# Sheet1.net
KiCad netlist of a schematic drawn in Altium Designer
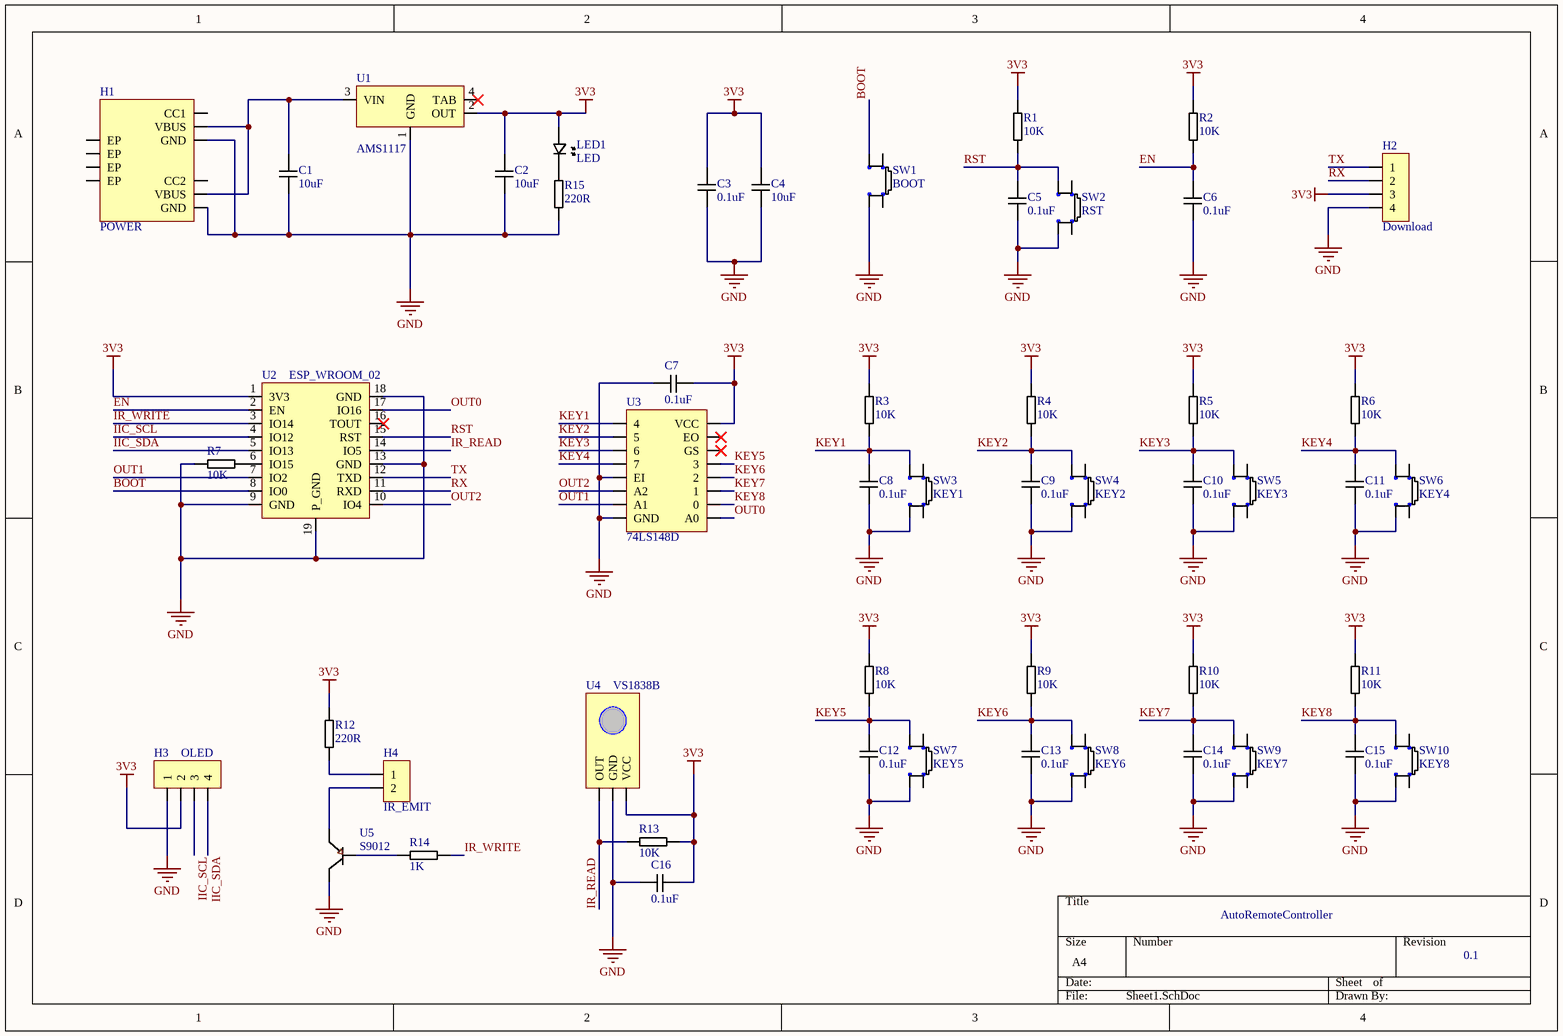
[diagram p0: Sheet1.SchDoc]

(export (version "E")
  (design (tool "Eeschema 10.0.6"))
  (components
    (comp (ref "C1")
      (value "10uF")
      (footprint "Capacity_0805_SMD")
      (libsource (lib "BasicLib") (part "Cap0805"))
    )
    (comp (ref "C2")
      (value "10uF")
      (footprint "Capacity_0805_SMD")
      (libsource (lib "BasicLib") (part "Cap0805"))
    )
    (comp (ref "C3")
      (value "0.1uF")
      (footprint "Capacity_0805_SMD")
      (libsource (lib "BasicLib") (part "Cap0805"))
    )
    (comp (ref "C4")
      (value "10uF")
      (footprint "Capacity_0805_SMD")
      (libsource (lib "BasicLib") (part "Cap0805"))
    )
    (comp (ref "C5")
      (value "0.1uF")
      (footprint "Capacity_0805_SMD")
      (libsource (lib "BasicLib") (part "Cap0805"))
    )
    (comp (ref "C6")
      (value "0.1uF")
      (footprint "Capacity_0805_SMD")
      (libsource (lib "BasicLib") (part "Cap0805"))
    )
    (comp (ref "C7")
      (value "0.1uF")
      (footprint "Capacity_0805_SMD")
      (libsource (lib "BasicLib") (part "Cap0805"))
    )
    (comp (ref "C8")
      (value "0.1uF")
      (footprint "Capacity_0805_SMD")
      (libsource (lib "BasicLib") (part "Cap0805"))
    )
    (comp (ref "C9")
      (value "0.1uF")
      (footprint "Capacity_0805_SMD")
      (libsource (lib "BasicLib") (part "Cap0805"))
    )
    (comp (ref "C10")
      (value "0.1uF")
      (footprint "Capacity_0805_SMD")
      (libsource (lib "BasicLib") (part "Cap0805"))
    )
    (comp (ref "C11")
      (value "0.1uF")
      (footprint "Capacity_0805_SMD")
      (libsource (lib "BasicLib") (part "Cap0805"))
    )
    (comp (ref "C12")
      (value "0.1uF")
      (footprint "Capacity_0805_SMD")
      (libsource (lib "BasicLib") (part "Cap0805"))
    )
    (comp (ref "C13")
      (value "0.1uF")
      (footprint "Capacity_0805_SMD")
      (libsource (lib "BasicLib") (part "Cap0805"))
    )
    (comp (ref "C14")
      (value "0.1uF")
      (footprint "Capacity_0805_SMD")
      (libsource (lib "BasicLib") (part "Cap0805"))
    )
    (comp (ref "C15")
      (value "0.1uF")
      (footprint "Capacity_0805_SMD")
      (libsource (lib "BasicLib") (part "Cap0805"))
    )
    (comp (ref "C16")
      (value "0.1uF")
      (footprint "Capacity_0805_SMD")
      (libsource (lib "BasicLib") (part "Cap0805"))
    )
    (comp (ref "H1")
      (value "POWER")
      (footprint "TYPEC_SMD_6P")
      (libsource (lib "ConnectorLib") (part "TYPEC_6P_SMD"))
    )
    (comp (ref "H2")
      (value "Download")
      (footprint "Header_2.54_1X4_TH")
      (libsource (lib "") (part "Header_2.54mm_1X4_TH_1"))
    )
    (comp (ref "H3")
      (value "OLED")
      (footprint "Header_2.54_1X4_TH")
      (libsource (lib "ConnectorLib") (part "Header_2.54mm_1X4_TH"))
    )
    (comp (ref "H4")
      (value "IR_EMIT")
      (footprint "Header_2.54_1X2_TH")
      (libsource (lib "ConnectorLib") (part "Header_2.54mm_1X2_TH"))
    )
    (comp (ref "LED1") (value "LED") (footprint "LED_0805_SMD") (libsource (lib "BasicLib") (part "LED0805")))
    (comp (ref "R1")
      (value "10K")
      (footprint "Resistance_0805_SMD")
      (libsource (lib "BasicLib") (part "Res0805"))
    )
    (comp (ref "R2")
      (value "10K")
      (footprint "Resistance_0805_SMD")
      (libsource (lib "BasicLib") (part "Res0805"))
    )
    (comp (ref "R3")
      (value "10K")
      (footprint "Resistance_0805_SMD")
      (libsource (lib "BasicLib") (part "Res0805"))
    )
    (comp (ref "R4")
      (value "10K")
      (footprint "Resistance_0805_SMD")
      (libsource (lib "BasicLib") (part "Res0805"))
    )
    (comp (ref "R5")
      (value "10K")
      (footprint "Resistance_0805_SMD")
      (libsource (lib "BasicLib") (part "Res0805"))
    )
    (comp (ref "R6")
      (value "10K")
      (footprint "Resistance_0805_SMD")
      (libsource (lib "BasicLib") (part "Res0805"))
    )
    (comp (ref "R7")
      (value "10K")
      (footprint "Resistance_0805_SMD")
      (libsource (lib "BasicLib") (part "Res0805"))
    )
    (comp (ref "R8")
      (value "10K")
      (footprint "Resistance_0805_SMD")
      (libsource (lib "BasicLib") (part "Res0805"))
    )
    (comp (ref "R9")
      (value "10K")
      (footprint "Resistance_0805_SMD")
      (libsource (lib "BasicLib") (part "Res0805"))
    )
    (comp (ref "R10")
      (value "10K")
      (footprint "Resistance_0805_SMD")
      (libsource (lib "BasicLib") (part "Res0805"))
    )
    (comp (ref "R11")
      (value "10K")
      (footprint "Resistance_0805_SMD")
      (libsource (lib "BasicLib") (part "Res0805"))
    )
    (comp (ref "R12")
      (value "220R")
      (footprint "Resistance_0805_SMD")
      (libsource (lib "BasicLib") (part "Res0805"))
    )
    (comp (ref "R13")
      (value "10K")
      (footprint "Resistance_0805_SMD")
      (libsource (lib "BasicLib") (part "Res0805"))
    )
    (comp (ref "R14")
      (value "1K")
      (footprint "Resistance_0805_SMD")
      (libsource (lib "BasicLib") (part "Res0805"))
    )
    (comp (ref "R15")
      (value "220R")
      (footprint "Resistance_0805_SMD")
      (libsource (lib "BasicLib") (part "Res0805"))
    )
    (comp (ref "SW1")
      (value "BOOT")
      (footprint "SW_6.0*6.0_SMD")
      (libsource (lib "BasicLib") (part "Key_6.0X6.0"))
    )
    (comp (ref "SW2")
      (value "RST")
      (footprint "SW_6.0*6.0_SMD")
      (libsource (lib "BasicLib") (part "Key_6.0X6.0"))
    )
    (comp (ref "SW3")
      (value "KEY1")
      (footprint "SW_6.0*6.0_SMD")
      (libsource (lib "BasicLib") (part "Key_6.0X6.0"))
    )
    (comp (ref "SW4")
      (value "KEY2")
      (footprint "SW_6.0*6.0_SMD")
      (libsource (lib "BasicLib") (part "Key_6.0X6.0"))
    )
    (comp (ref "SW5")
      (value "KEY3")
      (footprint "SW_6.0*6.0_SMD")
      (libsource (lib "BasicLib") (part "Key_6.0X6.0"))
    )
    (comp (ref "SW6")
      (value "KEY4")
      (footprint "SW_6.0*6.0_SMD")
      (libsource (lib "BasicLib") (part "Key_6.0X6.0"))
    )
    (comp (ref "SW7")
      (value "KEY5")
      (footprint "SW_6.0*6.0_SMD")
      (libsource (lib "BasicLib") (part "Key_6.0X6.0"))
    )
    (comp (ref "SW8")
      (value "KEY6")
      (footprint "SW_6.0*6.0_SMD")
      (libsource (lib "BasicLib") (part "Key_6.0X6.0"))
    )
    (comp (ref "SW9")
      (value "KEY7")
      (footprint "SW_6.0*6.0_SMD")
      (libsource (lib "BasicLib") (part "Key_6.0X6.0"))
    )
    (comp (ref "SW10")
      (value "KEY8")
      (footprint "SW_6.0*6.0_SMD")
      (libsource (lib "BasicLib") (part "Key_6.0X6.0"))
    )
    (comp (ref "U1") (value "AMS1117") (footprint "AMS1117") (libsource (lib "ICLib") (part "AMS1117")))
    (comp (ref "U2")
      (value "ESP_WROOM_02")
      (footprint "ESP_WROOM_02")
      (libsource (lib "ESPLib") (part "ESP_WROOM_02"))
    )
    (comp (ref "U3") (value "74LS148D") (footprint "SOIC-16") (libsource (lib "ICLib") (part "74LS148D")))
    (comp (ref "U4") (value "VS1838B") (footprint "VS1838B") (libsource (lib "BasicLib") (part "VS1838B")))
    (comp (ref "U5") (value "S9012") (footprint "SOT-23") (libsource (lib "BasicLib") (part "S9012_PNP")))
  )
  (nets
    (net (code "1") (name "/BOOT") (class "Default")
      (node (ref "SW1") (pin "2") (pinfunction "2_2") (pintype "passive"))
      (node (ref "U2") (pin "8") (pinfunction "IO0_8") (pintype "passive"))
    )
    (net (code "2") (name "/EN") (class "Default")
      (node (ref "C6") (pin "2") (pinfunction "2_2") (pintype "passive"))
      (node (ref "R2") (pin "1") (pinfunction "1_1") (pintype "passive"))
      (node (ref "U2") (pin "2") (pinfunction "EN_2") (pintype "passive"))
    )
    (net (code "3") (name "/IIC_SCL") (class "Default")
      (node (ref "H3") (pin "3") (pinfunction "3_3") (pintype "passive"))
      (node (ref "U2") (pin "4") (pinfunction "IO12_4") (pintype "passive"))
    )
    (net (code "4") (name "/IIC_SDA") (class "Default")
      (node (ref "H3") (pin "4") (pinfunction "4_4") (pintype "passive"))
      (node (ref "U2") (pin "5") (pinfunction "IO13_5") (pintype "passive"))
    )
    (net (code "5") (name "/IR_READ") (class "Default")
      (node (ref "R13") (pin "2") (pinfunction "2_2") (pintype "passive"))
      (node (ref "U2") (pin "14") (pinfunction "IO5_14") (pintype "passive"))
      (node (ref "U4") (pin "1") (pinfunction "OUT_1") (pintype "passive"))
    )
    (net (code "6") (name "/IR_WRITE") (class "Default")
      (node (ref "R14") (pin "2") (pinfunction "2_2") (pintype "passive"))
      (node (ref "U2") (pin "3") (pinfunction "IO14_3") (pintype "passive"))
    )
    (net (code "7") (name "/KEY1") (class "Default")
      (node (ref "C8") (pin "2") (pinfunction "2_2") (pintype "passive"))
      (node (ref "R3") (pin "1") (pinfunction "1_1") (pintype "passive"))
      (node (ref "SW3") (pin "2") (pinfunction "2_2") (pintype "passive"))
      (node (ref "U3") (pin "1") (pinfunction "4_1") (pintype "passive"))
    )
    (net (code "8") (name "/KEY2") (class "Default")
      (node (ref "C9") (pin "2") (pinfunction "2_2") (pintype "passive"))
      (node (ref "R4") (pin "1") (pinfunction "1_1") (pintype "passive"))
      (node (ref "SW4") (pin "2") (pinfunction "2_2") (pintype "passive"))
      (node (ref "U3") (pin "2") (pinfunction "5_2") (pintype "passive"))
    )
    (net (code "9") (name "/KEY3") (class "Default")
      (node (ref "C10") (pin "2") (pinfunction "2_2") (pintype "passive"))
      (node (ref "R5") (pin "1") (pinfunction "1_1") (pintype "passive"))
      (node (ref "SW5") (pin "2") (pinfunction "2_2") (pintype "passive"))
      (node (ref "U3") (pin "3") (pinfunction "6_3") (pintype "passive"))
    )
    (net (code "10") (name "/KEY4") (class "Default")
      (node (ref "C11") (pin "2") (pinfunction "2_2") (pintype "passive"))
      (node (ref "R6") (pin "1") (pinfunction "1_1") (pintype "passive"))
      (node (ref "SW6") (pin "2") (pinfunction "2_2") (pintype "passive"))
      (node (ref "U3") (pin "4") (pinfunction "7_4") (pintype "passive"))
    )
    (net (code "11") (name "/KEY5") (class "Default")
      (node (ref "C12") (pin "2") (pinfunction "2_2") (pintype "passive"))
      (node (ref "R8") (pin "1") (pinfunction "1_1") (pintype "passive"))
      (node (ref "SW7") (pin "2") (pinfunction "2_2") (pintype "passive"))
      (node (ref "U3") (pin "13") (pinfunction "3_13") (pintype "passive"))
    )
    (net (code "12") (name "/KEY6") (class "Default")
      (node (ref "C13") (pin "2") (pinfunction "2_2") (pintype "passive"))
      (node (ref "R9") (pin "1") (pinfunction "1_1") (pintype "passive"))
      (node (ref "SW8") (pin "2") (pinfunction "2_2") (pintype "passive"))
      (node (ref "U3") (pin "12") (pinfunction "2_12") (pintype "passive"))
    )
    (net (code "13") (name "/KEY7") (class "Default")
      (node (ref "C14") (pin "2") (pinfunction "2_2") (pintype "passive"))
      (node (ref "R10") (pin "1") (pinfunction "1_1") (pintype "passive"))
      (node (ref "SW9") (pin "2") (pinfunction "2_2") (pintype "passive"))
      (node (ref "U3") (pin "11") (pinfunction "1_11") (pintype "passive"))
    )
    (net (code "14") (name "/KEY8") (class "Default")
      (node (ref "C15") (pin "2") (pinfunction "2_2") (pintype "passive"))
      (node (ref "R11") (pin "1") (pinfunction "1_1") (pintype "passive"))
      (node (ref "SW10") (pin "2") (pinfunction "2_2") (pintype "passive"))
      (node (ref "U3") (pin "10") (pinfunction "0_10") (pintype "passive"))
    )
    (net (code "15") (name "/OUT0") (class "Default")
      (node (ref "U2") (pin "17") (pinfunction "IO16_17") (pintype "passive"))
      (node (ref "U3") (pin "9") (pinfunction "A0_9") (pintype "passive"))
    )
    (net (code "16") (name "/OUT1") (class "Default")
      (node (ref "U2") (pin "7") (pinfunction "IO2_7") (pintype "passive"))
      (node (ref "U3") (pin "7") (pinfunction "A1_7") (pintype "passive"))
    )
    (net (code "17") (name "/OUT2") (class "Default")
      (node (ref "U2") (pin "10") (pinfunction "IO4_10") (pintype "passive"))
      (node (ref "U3") (pin "6") (pinfunction "A2_6") (pintype "passive"))
    )
    (net (code "18") (name "/RST") (class "Default")
      (node (ref "C5") (pin "2") (pinfunction "2_2") (pintype "passive"))
      (node (ref "R1") (pin "1") (pinfunction "1_1") (pintype "passive"))
      (node (ref "SW2") (pin "2") (pinfunction "2_2") (pintype "passive"))
      (node (ref "U2") (pin "15") (pinfunction "RST_15") (pintype "passive"))
    )
    (net (code "19") (name "/RX") (class "Default")
      (node (ref "H2") (pin "2") (pinfunction "2_2") (pintype "passive"))
      (node (ref "U2") (pin "11") (pinfunction "RXD_11") (pintype "passive"))
    )
    (net (code "20") (name "/TX") (class "Default")
      (node (ref "H2") (pin "1") (pinfunction "1_1") (pintype "passive"))
      (node (ref "U2") (pin "12") (pinfunction "TXD_12") (pintype "passive"))
    )
    (net (code "21") (name "3V3") (class "Default")
      (node (ref "C16") (pin "1") (pinfunction "1_1") (pintype "passive"))
      (node (ref "C2") (pin "2") (pinfunction "2_2") (pintype "passive"))
      (node (ref "C3") (pin "2") (pinfunction "2_2") (pintype "passive"))
      (node (ref "C4") (pin "2") (pinfunction "2_2") (pintype "passive"))
      (node (ref "C7") (pin "1") (pinfunction "1_1") (pintype "passive"))
      (node (ref "H2") (pin "3") (pinfunction "3_3") (pintype "passive"))
      (node (ref "H3") (pin "2") (pinfunction "2_2") (pintype "passive"))
      (node (ref "LED1") (pin "1") (pinfunction "1_1") (pintype "passive"))
      (node (ref "R1") (pin "2") (pinfunction "2_2") (pintype "passive"))
      (node (ref "R10") (pin "2") (pinfunction "2_2") (pintype "passive"))
      (node (ref "R11") (pin "2") (pinfunction "2_2") (pintype "passive"))
      (node (ref "R12") (pin "2") (pinfunction "2_2") (pintype "passive"))
      (node (ref "R13") (pin "1") (pinfunction "1_1") (pintype "passive"))
      (node (ref "R2") (pin "2") (pinfunction "2_2") (pintype "passive"))
      (node (ref "R3") (pin "2") (pinfunction "2_2") (pintype "passive"))
      (node (ref "R4") (pin "2") (pinfunction "2_2") (pintype "passive"))
      (node (ref "R5") (pin "2") (pinfunction "2_2") (pintype "passive"))
      (node (ref "R6") (pin "2") (pinfunction "2_2") (pintype "passive"))
      (node (ref "R8") (pin "2") (pinfunction "2_2") (pintype "passive"))
      (node (ref "R9") (pin "2") (pinfunction "2_2") (pintype "passive"))
      (node (ref "U1") (pin "2") (pinfunction "OUT_2") (pintype "passive"))
      (node (ref "U2") (pin "1") (pinfunction "3V3_1") (pintype "passive"))
      (node (ref "U3") (pin "16") (pinfunction "VCC_16") (pintype "passive"))
      (node (ref "U4") (pin "3") (pinfunction "VCC_3") (pintype "passive"))
    )
    (net (code "22") (name "GND") (class "Default")
      (node (ref "C1") (pin "1") (pinfunction "1_1") (pintype "passive"))
      (node (ref "C10") (pin "1") (pinfunction "1_1") (pintype "passive"))
      (node (ref "C11") (pin "1") (pinfunction "1_1") (pintype "passive"))
      (node (ref "C12") (pin "1") (pinfunction "1_1") (pintype "passive"))
      (node (ref "C13") (pin "1") (pinfunction "1_1") (pintype "passive"))
      (node (ref "C14") (pin "1") (pinfunction "1_1") (pintype "passive"))
      (node (ref "C15") (pin "1") (pinfunction "1_1") (pintype "passive"))
      (node (ref "C16") (pin "2") (pinfunction "2_2") (pintype "passive"))
      (node (ref "C2") (pin "1") (pinfunction "1_1") (pintype "passive"))
      (node (ref "C3") (pin "1") (pinfunction "1_1") (pintype "passive"))
      (node (ref "C4") (pin "1") (pinfunction "1_1") (pintype "passive"))
      (node (ref "C5") (pin "1") (pinfunction "1_1") (pintype "passive"))
      (node (ref "C6") (pin "1") (pinfunction "1_1") (pintype "passive"))
      (node (ref "C7") (pin "2") (pinfunction "2_2") (pintype "passive"))
      (node (ref "C8") (pin "1") (pinfunction "1_1") (pintype "passive"))
      (node (ref "C9") (pin "1") (pinfunction "1_1") (pintype "passive"))
      (node (ref "H1") (pin "A12") (pinfunction "GND_A12") (pintype "passive"))
      (node (ref "H1") (pin "B12") (pinfunction "GND_B12") (pintype "passive"))
      (node (ref "H2") (pin "4") (pinfunction "4_4") (pintype "passive"))
      (node (ref "H3") (pin "1") (pinfunction "1_1") (pintype "passive"))
      (node (ref "R15") (pin "1") (pinfunction "1_1") (pintype "passive"))
      (node (ref "R7") (pin "2") (pinfunction "2_2") (pintype "passive"))
      (node (ref "SW1") (pin "4") (pinfunction "4_4") (pintype "passive"))
      (node (ref "SW10") (pin "4") (pinfunction "4_4") (pintype "passive"))
      (node (ref "SW2") (pin "4") (pinfunction "4_4") (pintype "passive"))
      (node (ref "SW3") (pin "4") (pinfunction "4_4") (pintype "passive"))
      (node (ref "SW4") (pin "4") (pinfunction "4_4") (pintype "passive"))
      (node (ref "SW5") (pin "4") (pinfunction "4_4") (pintype "passive"))
      (node (ref "SW6") (pin "4") (pinfunction "4_4") (pintype "passive"))
      (node (ref "SW7") (pin "4") (pinfunction "4_4") (pintype "passive"))
      (node (ref "SW8") (pin "4") (pinfunction "4_4") (pintype "passive"))
      (node (ref "SW9") (pin "4") (pinfunction "4_4") (pintype "passive"))
      (node (ref "U1") (pin "1") (pinfunction "GND_1") (pintype "passive"))
      (node (ref "U2") (pin "13") (pinfunction "GND_13") (pintype "passive"))
      (node (ref "U2") (pin "18") (pinfunction "GND_18") (pintype "passive"))
      (node (ref "U2") (pin "19") (pinfunction "P_GND_19") (pintype "passive"))
      (node (ref "U2") (pin "9") (pinfunction "GND_9") (pintype "passive"))
      (node (ref "U3") (pin "5") (pinfunction "EI_5") (pintype "passive"))
      (node (ref "U3") (pin "8") (pinfunction "GND_8") (pintype "passive"))
      (node (ref "U4") (pin "2") (pinfunction "GND_2") (pintype "passive"))
      (node (ref "U5") (pin "3") (pinfunction "3_3") (pintype "passive"))
    )
    (net (code "23") (name "Net-(H4-Pad1)") (class "Default")
      (node (ref "H4") (pin "1") (pinfunction "1_1") (pintype "passive"))
      (node (ref "R12") (pin "1") (pinfunction "1_1") (pintype "passive"))
    )
    (net (code "24") (name "Net-(H4-Pad2)") (class "Default")
      (node (ref "H4") (pin "2") (pinfunction "2_2") (pintype "passive"))
      (node (ref "U5") (pin "2") (pinfunction "2_2") (pintype "passive"))
    )
    (net (code "25") (name "Net-(LED1-Pad2)") (class "Default")
      (node (ref "LED1") (pin "2") (pinfunction "2_2") (pintype "passive"))
      (node (ref "R15") (pin "2") (pinfunction "2_2") (pintype "passive"))
    )
    (net (code "26") (name "Net-(R14-Pad1)") (class "Default")
      (node (ref "R14") (pin "1") (pinfunction "1_1") (pintype "passive"))
      (node (ref "U5") (pin "1") (pinfunction "1_1") (pintype "passive"))
    )
    (net (code "27") (name "Net-(U1-VIN)") (class "Default")
      (node (ref "C1") (pin "2") (pinfunction "2_2") (pintype "passive"))
      (node (ref "H1") (pin "A9") (pinfunction "VBUS_A9") (pintype "passive"))
      (node (ref "H1") (pin "B9") (pinfunction "VBUS_B9") (pintype "passive"))
      (node (ref "U1") (pin "3") (pinfunction "VIN_3") (pintype "passive"))
    )
    (net (code "28") (name "Net-(U2-IO15)") (class "Default")
      (node (ref "R7") (pin "1") (pinfunction "1_1") (pintype "passive"))
      (node (ref "U2") (pin "6") (pinfunction "IO15_6") (pintype "passive"))
    )
    (net (code "29") (name "unconnected-(H1-CC1-PadA5)") (class "Default")
      (node (ref "H1") (pin "A5") (pinfunction "CC1_A5") (pintype "passive"))
    )
    (net (code "30") (name "unconnected-(H1-CC2-PadB5)") (class "Default")
      (node (ref "H1") (pin "B5") (pinfunction "CC2_B5") (pintype "passive"))
    )
    (net (code "31") (name "unconnected-(H1-EP-Pad1)") (class "Default")
      (node (ref "H1") (pin "1") (pinfunction "EP_1") (pintype "passive"))
    )
    (net (code "32") (name "unconnected-(H1-EP-Pad2)") (class "Default")
      (node (ref "H1") (pin "2") (pinfunction "EP_2") (pintype "passive"))
    )
    (net (code "33") (name "unconnected-(H1-EP-Pad3)") (class "Default")
      (node (ref "H1") (pin "3") (pinfunction "EP_3") (pintype "passive"))
    )
    (net (code "34") (name "unconnected-(H1-EP-Pad4)") (class "Default")
      (node (ref "H1") (pin "4") (pinfunction "EP_4") (pintype "passive"))
    )
    (net (code "35") (name "unconnected-(SW1-Pad1)") (class "Default")
      (node (ref "SW1") (pin "1") (pinfunction "1_1") (pintype "passive"))
    )
    (net (code "36") (name "unconnected-(SW1-Pad3)") (class "Default")
      (node (ref "SW1") (pin "3") (pinfunction "3_3") (pintype "passive"))
    )
    (net (code "37") (name "unconnected-(SW2-Pad1)") (class "Default")
      (node (ref "SW2") (pin "1") (pinfunction "1_1") (pintype "passive"))
    )
    (net (code "38") (name "unconnected-(SW2-Pad3)") (class "Default")
      (node (ref "SW2") (pin "3") (pinfunction "3_3") (pintype "passive"))
    )
    (net (code "39") (name "unconnected-(SW3-Pad1)") (class "Default")
      (node (ref "SW3") (pin "1") (pinfunction "1_1") (pintype "passive"))
    )
    (net (code "40") (name "unconnected-(SW3-Pad3)") (class "Default")
      (node (ref "SW3") (pin "3") (pinfunction "3_3") (pintype "passive"))
    )
    (net (code "41") (name "unconnected-(SW4-Pad1)") (class "Default")
      (node (ref "SW4") (pin "1") (pinfunction "1_1") (pintype "passive"))
    )
    (net (code "42") (name "unconnected-(SW4-Pad3)") (class "Default")
      (node (ref "SW4") (pin "3") (pinfunction "3_3") (pintype "passive"))
    )
    (net (code "43") (name "unconnected-(SW5-Pad1)") (class "Default")
      (node (ref "SW5") (pin "1") (pinfunction "1_1") (pintype "passive"))
    )
    (net (code "44") (name "unconnected-(SW5-Pad3)") (class "Default")
      (node (ref "SW5") (pin "3") (pinfunction "3_3") (pintype "passive"))
    )
    (net (code "45") (name "unconnected-(SW6-Pad1)") (class "Default")
      (node (ref "SW6") (pin "1") (pinfunction "1_1") (pintype "passive"))
    )
    (net (code "46") (name "unconnected-(SW6-Pad3)") (class "Default")
      (node (ref "SW6") (pin "3") (pinfunction "3_3") (pintype "passive"))
    )
    (net (code "47") (name "unconnected-(SW7-Pad1)") (class "Default")
      (node (ref "SW7") (pin "1") (pinfunction "1_1") (pintype "passive"))
    )
    (net (code "48") (name "unconnected-(SW7-Pad3)") (class "Default")
      (node (ref "SW7") (pin "3") (pinfunction "3_3") (pintype "passive"))
    )
    (net (code "49") (name "unconnected-(SW8-Pad1)") (class "Default")
      (node (ref "SW8") (pin "1") (pinfunction "1_1") (pintype "passive"))
    )
    (net (code "50") (name "unconnected-(SW8-Pad3)") (class "Default")
      (node (ref "SW8") (pin "3") (pinfunction "3_3") (pintype "passive"))
    )
    (net (code "51") (name "unconnected-(SW9-Pad1)") (class "Default")
      (node (ref "SW9") (pin "1") (pinfunction "1_1") (pintype "passive"))
    )
    (net (code "52") (name "unconnected-(SW9-Pad3)") (class "Default")
      (node (ref "SW9") (pin "3") (pinfunction "3_3") (pintype "passive"))
    )
    (net (code "53") (name "unconnected-(SW10-Pad1)") (class "Default")
      (node (ref "SW10") (pin "1") (pinfunction "1_1") (pintype "passive"))
    )
    (net (code "54") (name "unconnected-(SW10-Pad3)") (class "Default")
      (node (ref "SW10") (pin "3") (pinfunction "3_3") (pintype "passive"))
    )
    (net (code "55") (name "unconnected-(U1-TAB-Pad4)") (class "Default")
      (node (ref "U1") (pin "4") (pinfunction "TAB_4") (pintype "passive+no_connect"))
    )
    (net (code "56") (name "unconnected-(U2-TOUT-Pad16)") (class "Default")
      (node (ref "U2") (pin "16") (pinfunction "TOUT_16") (pintype "passive+no_connect"))
    )
    (net (code "57") (name "unconnected-(U3-EO-Pad15)") (class "Default")
      (node (ref "U3") (pin "15") (pinfunction "EO_15") (pintype "passive+no_connect"))
    )
    (net (code "58") (name "unconnected-(U3-GS-Pad14)") (class "Default")
      (node (ref "U3") (pin "14") (pinfunction "GS_14") (pintype "passive+no_connect"))
    )
  )
)
